# PelletMonV3.net
KiCad netlist of a schematic drawn in EasyEDA Pro
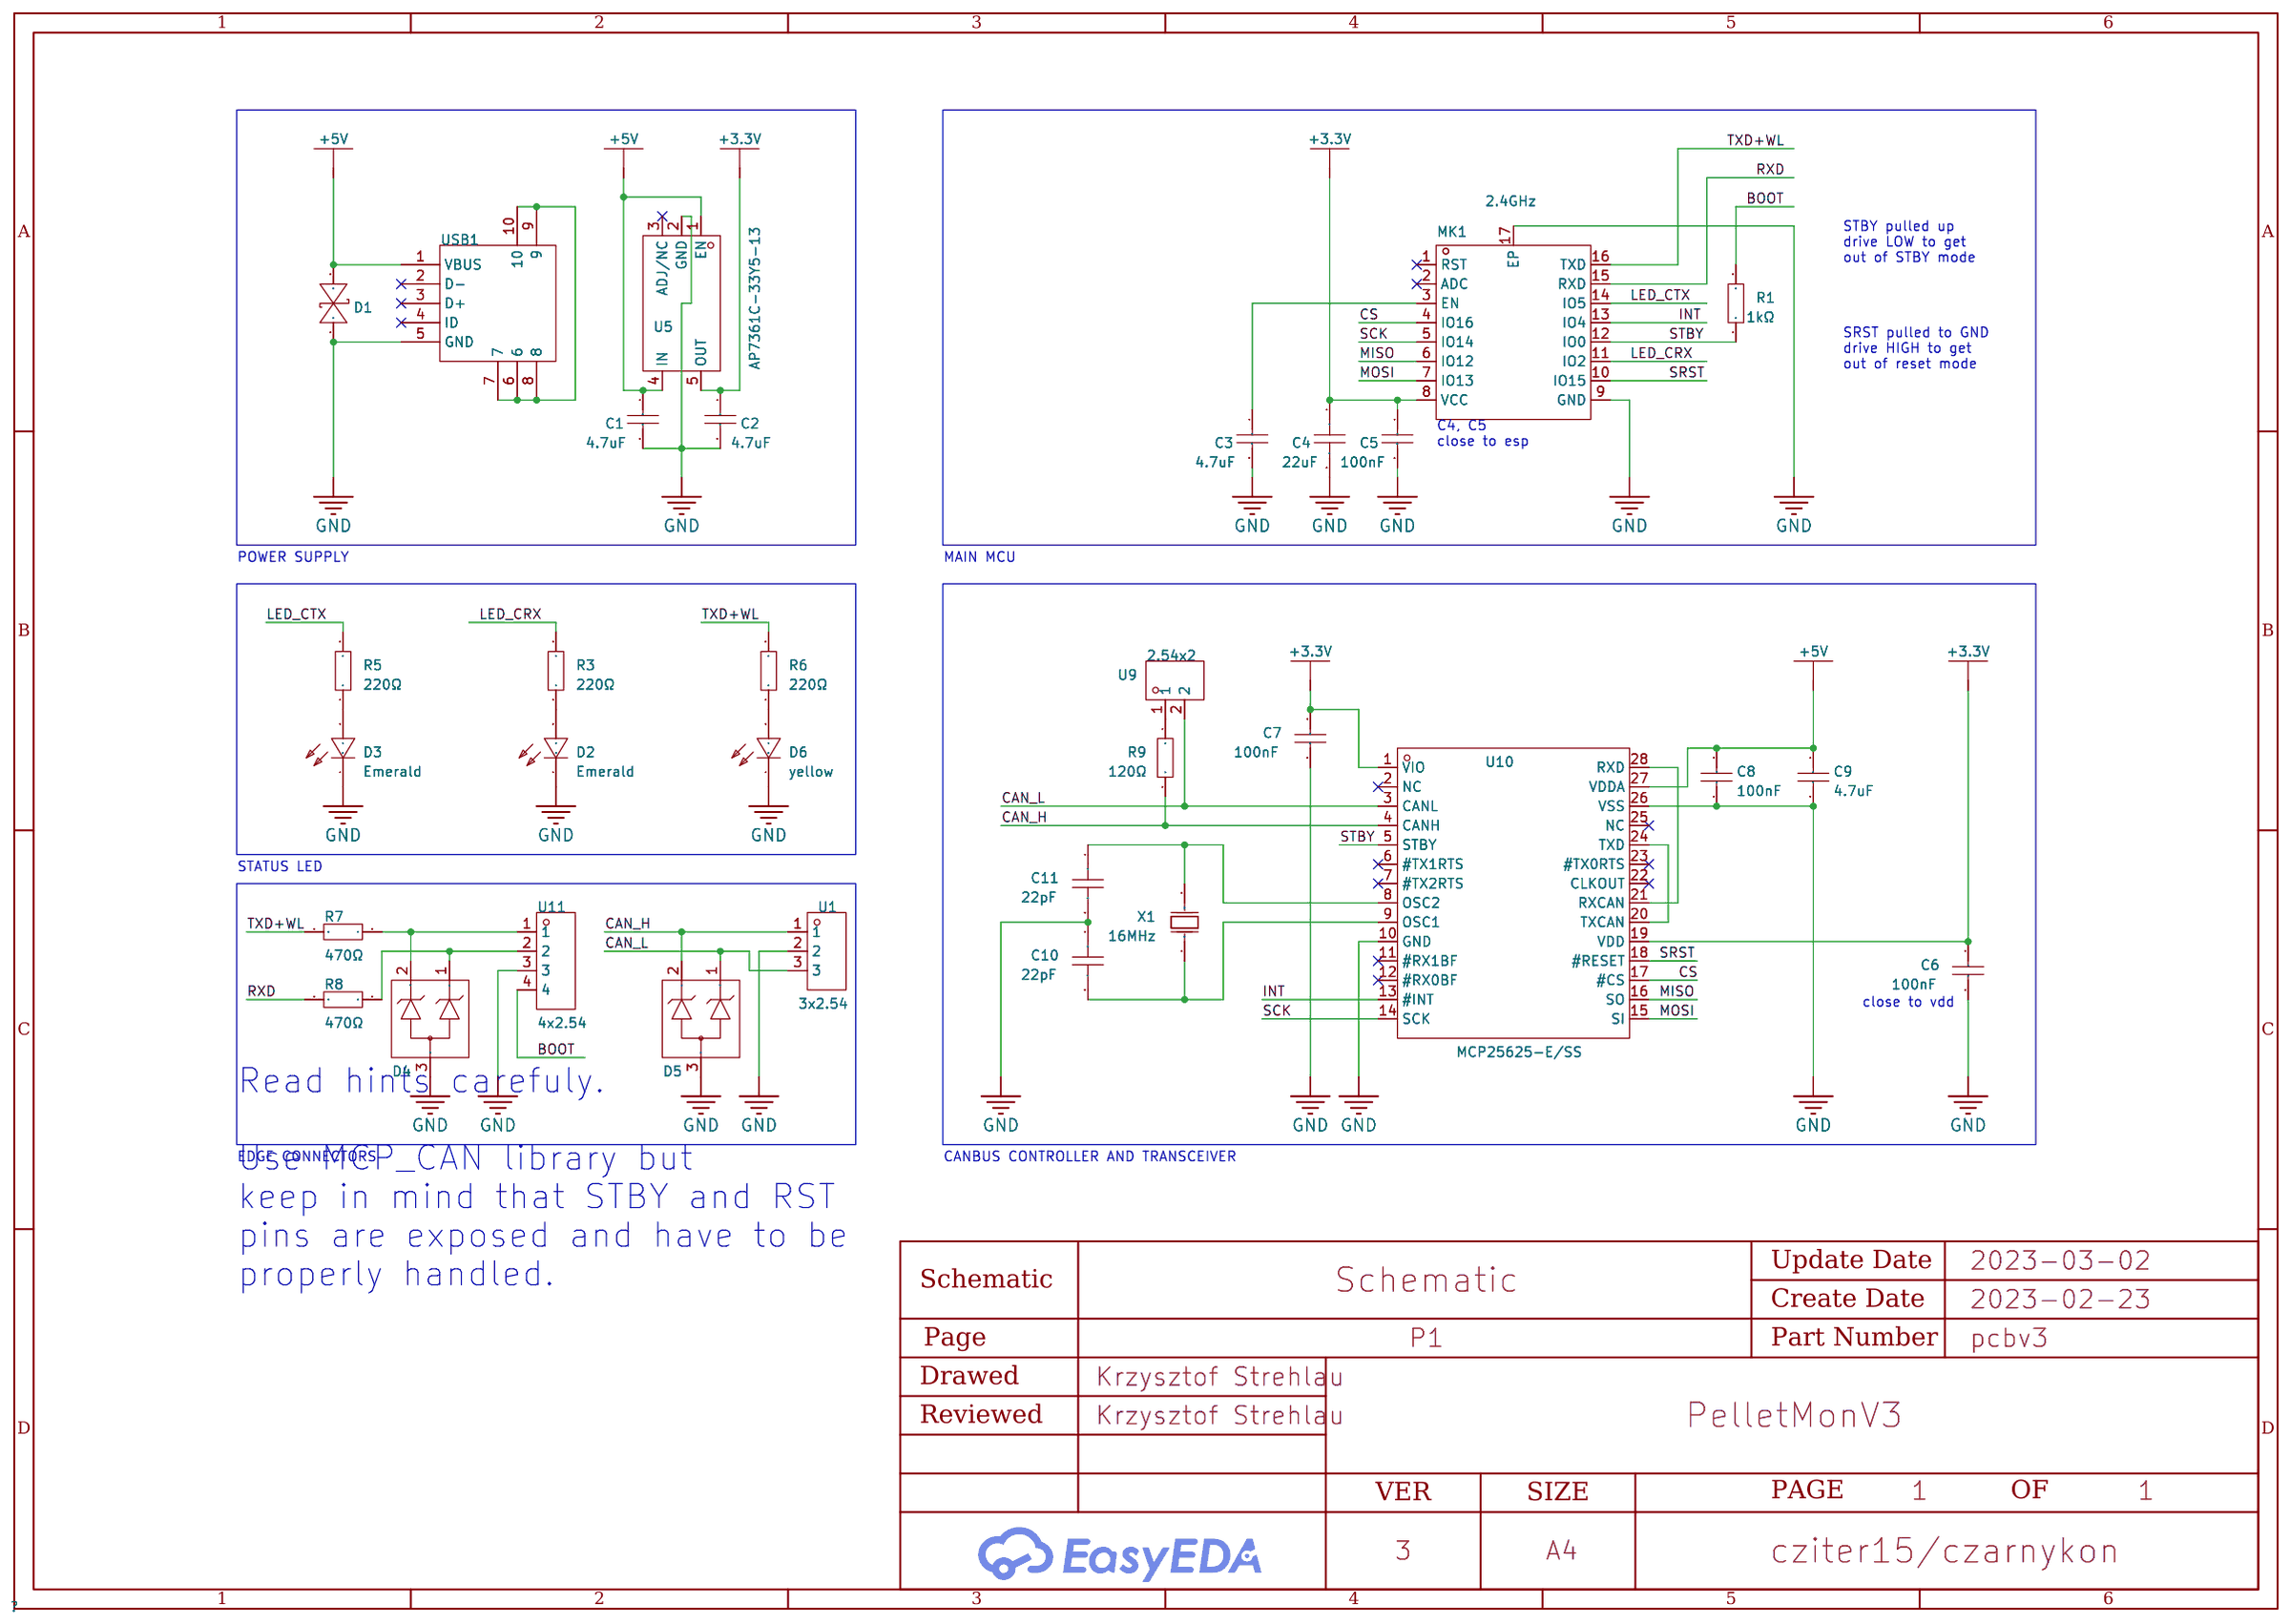
[diagram p0: schematic sheet]

(export (version "E")
  (design (tool "Eeschema 10.0.6"))
  (components
    (comp (ref "C1")
      (value "4.7uF")
      (footprint "easyedapro:C0805")
      (fields
        (field (name "Manufacturer Part") "CL21A475KAQNNNE")
        (field (name "Manufacturer") "SAMSUNG(三星)")
        (field (name "Tolerance") "±10%")
      )
      (libsource (lib "easyedapro") (part "CL21A475KAQNNNE"))
    )
    (comp (ref "C2")
      (value "4.7uF")
      (footprint "easyedapro:C0805")
      (fields
        (field (name "Manufacturer Part") "CL21A475KAQNNNE")
        (field (name "Manufacturer") "SAMSUNG(三星)")
        (field (name "Tolerance") "±10%")
      )
      (libsource (lib "easyedapro") (part "CL21A475KAQNNNE"))
    )
    (comp (ref "C3")
      (value "4.7uF")
      (footprint "easyedapro:C0805")
      (fields
        (field (name "Manufacturer Part") "CL21A475KAQNNNE")
        (field (name "Manufacturer") "SAMSUNG(三星)")
        (field (name "Tolerance") "±10%")
      )
      (libsource (lib "easyedapro") (part "CL21A475KAQNNNE"))
    )
    (comp (ref "C4")
      (value "22uF")
      (footprint "easyedapro:C0805")
      (fields
        (field (name "Manufacturer Part") "CL21A226MAQNNNE")
        (field (name "Manufacturer") "SAMSUNG(三星)")
        (field (name "Tolerance") "±20%")
      )
      (libsource (lib "easyedapro") (part "CL21A226MAQNNNE"))
    )
    (comp (ref "C5")
      (value "100nF")
      (footprint "easyedapro:C0805")
      (fields
        (field (name "Manufacturer Part") "CC0603KRX7R9BB104")
        (field (name "Manufacturer") "YAGEO(国巨)")
        (field (name "Tolerance") "±10%")
      )
      (libsource (lib "easyedapro") (part "CL21A475KAQNNNE"))
    )
    (comp (ref "C6")
      (value "100nF")
      (footprint "easyedapro:C0805")
      (fields
        (field (name "Manufacturer Part") "CC0603KRX7R9BB104")
        (field (name "Manufacturer") "YAGEO(国巨)")
        (field (name "Tolerance") "±10%")
      )
      (libsource (lib "easyedapro") (part "CL21A475KAQNNNE"))
    )
    (comp (ref "C7")
      (value "100nF")
      (footprint "easyedapro:C0805")
      (fields
        (field (name "Manufacturer Part") "CC0603KRX7R9BB104")
        (field (name "Manufacturer") "YAGEO(国巨)")
        (field (name "Tolerance") "±10%")
      )
      (libsource (lib "easyedapro") (part "CL21A475KAQNNNE"))
    )
    (comp (ref "C8")
      (value "100nF")
      (footprint "easyedapro:C0805")
      (fields
        (field (name "Manufacturer Part") "CC0603KRX7R9BB104")
        (field (name "Manufacturer") "YAGEO(国巨)")
        (field (name "Tolerance") "±10%")
      )
      (libsource (lib "easyedapro") (part "CL21A475KAQNNNE"))
    )
    (comp (ref "C9")
      (value "4.7uF")
      (footprint "easyedapro:C0805")
      (fields
        (field (name "Manufacturer Part") "CL21A475KAQNNNE")
        (field (name "Manufacturer") "SAMSUNG(三星)")
        (field (name "Tolerance") "±10%")
      )
      (libsource (lib "easyedapro") (part "CL21A475KAQNNNE"))
    )
    (comp (ref "C10")
      (value "22pF")
      (footprint "easyedapro:C0603")
      (fields
        (field (name "Manufacturer Part") "CC0603FRNPO9BN220")
        (field (name "Manufacturer") "YAGEO(国巨)")
        (field (name "Tolerance") "±1%")
      )
      (libsource (lib "easyedapro") (part "CC0603FRNPO9BN220"))
    )
    (comp (ref "C11")
      (value "22pF")
      (footprint "easyedapro:C0603")
      (fields
        (field (name "Manufacturer Part") "CC0603FRNPO9BN220")
        (field (name "Manufacturer") "YAGEO(国巨)")
      )
      (libsource (lib "easyedapro") (part "CC0603FRNPO9BN220"))
    )
    (comp (ref "D1")
      (value "PESD0603-240")
      (footprint "easyedapro:D0603-BI")
      (fields (field (name "Manufacturer") "Brightking(君耀电子)"))
      (libsource (lib "easyedapro") (part "TPESD5B5.0ST1G"))
    )
    (comp (ref "D2")
      (value "Emerald")
      (footprint "easyedapro:LED0603-RD")
      (fields
        (field (name "Manufacturer Part") "19-217/GHC-YR1S2/3T")
        (field (name "Manufacturer") "EVERLIGHT(亿光)")
      )
      (libsource (lib "easyedapro") (part "19-217/GHC-YR1S2/3T"))
    )
    (comp (ref "D3")
      (value "Emerald")
      (footprint "easyedapro:LED0603-RD")
      (fields
        (field (name "Manufacturer Part") "19-217/GHC-YR1S2/3T")
        (field (name "Manufacturer") "EVERLIGHT(亿光)")
      )
      (libsource (lib "easyedapro") (part "19-217/GHC-YR1S2/3T"))
    )
    (comp (ref "D4")
      (value "PESD3V3S2UT")
      (footprint "easyedapro:SOT-23-3_L2.9-W1.3-P1.90-LS2.4-BR")
      (fields (field (name "Manufacturer") "DOWO(东沃)"))
      (libsource (lib "easyedapro") (part "PESD3V3S2UT"))
    )
    (comp (ref "D5")
      (value "PESD2CAN")
      (footprint "easyedapro:SOT-23-3_L2.9-W1.3-P1.90-LS2.4-BR")
      (fields (field (name "Manufacturer") "DOWO(东沃)"))
      (libsource (lib "easyedapro") (part "PESD3V3S2UT"))
    )
    (comp (ref "D6")
      (value "yellow")
      (footprint "easyedapro:LED0603-RD")
      (fields
        (field (name "Manufacturer Part") "19-213/Y2C-CQ2R2L/3T(CY)")
        (field (name "Manufacturer") "EVERLIGHT(亿光)")
      )
      (libsource (lib "easyedapro") (part "19-213/Y2C-CQ2R2L/3T(CY)"))
    )
    (comp (ref "MK1")
      (value "2.4GHz")
      (footprint "easyedapro:WIRELM-SMD_ESP-07S")
      (fields (field (name "Manufacturer Part") "ESP-07S") (field (name "Manufacturer") "Ai-Thinker(安信可)"))
      (libsource (lib "easyedapro") (part "ESP-07S"))
    )
    (comp (ref "R1")
      (value "1kΩ")
      (footprint "easyedapro:R0603")
      (fields
        (field (name "Manufacturer Part") "0603WAF1001T5E")
        (field (name "Manufacturer") "UNI-ROYAL(厚声)")
        (field (name "Tolerance") "±1%")
      )
      (libsource (lib "easyedapro") (part "Res"))
    )
    (comp (ref "R3")
      (value "220Ω")
      (footprint "easyedapro:R0603")
      (fields
        (field (name "Manufacturer Part") "0603WAF2200T5E")
        (field (name "Manufacturer") "UNI-ROYAL(厚声)")
        (field (name "Tolerance") "±1%")
      )
      (libsource (lib "easyedapro") (part "0603WAF2200T5E"))
    )
    (comp (ref "R5")
      (value "220Ω")
      (footprint "easyedapro:R0603")
      (fields
        (field (name "Manufacturer Part") "0603WAF2200T5E")
        (field (name "Manufacturer") "UNI-ROYAL(厚声)")
        (field (name "Tolerance") "±1%")
      )
      (libsource (lib "easyedapro") (part "0603WAF2200T5E"))
    )
    (comp (ref "R6")
      (value "220Ω")
      (footprint "easyedapro:R0603")
      (fields
        (field (name "Manufacturer Part") "0603WAF2200T5E")
        (field (name "Manufacturer") "UNI-ROYAL(厚声)")
        (field (name "Tolerance") "±1%")
      )
      (libsource (lib "easyedapro") (part "0603WAF2200T5E"))
    )
    (comp (ref "R7")
      (value "470Ω")
      (footprint "easyedapro:R0603")
      (fields
        (field (name "Manufacturer Part") "0603WAF4700T5E")
        (field (name "Manufacturer") "UNI-ROYAL(厚声)")
        (field (name "Tolerance") "±1%")
      )
      (libsource (lib "easyedapro") (part "0805W8F1052T5E"))
    )
    (comp (ref "R8")
      (value "470Ω")
      (footprint "easyedapro:R0603")
      (fields
        (field (name "Manufacturer Part") "0603WAF4700T5E")
        (field (name "Manufacturer") "UNI-ROYAL(厚声)")
        (field (name "Tolerance") "±1%")
      )
      (libsource (lib "easyedapro") (part "0805W8F1052T5E"))
    )
    (comp (ref "R9")
      (value "120Ω")
      (footprint "easyedapro:R0603")
      (fields
        (field (name "Manufacturer Part") "0603WAF1200T5E")
        (field (name "Manufacturer") "UNI-ROYAL(厚声)")
        (field (name "Tolerance") "±1%")
      )
      (libsource (lib "easyedapro") (part "Res"))
    )
    (comp (ref "U1")
      (value "3x2.54")
      (footprint "easyedapro:CONN-TH_DB125-2.54-3P-GN")
      (fields (field (name "Manufacturer") "DIBO(地博电气)"))
      (libsource (lib "easyedapro") (part "DB125-2.54-3P-GN"))
    )
    (comp (ref "U5")
      (value "AP7361C-33Y5-13")
      (footprint "easyedapro:SOT-89-5_L4.5-W2.5-P1.50-LS4.5-BR")
      (fields (field (name "Manufacturer") "DIODES(美台)"))
      (libsource (lib "easyedapro") (part "AP7361C-33Y5-13"))
    )
    (comp (ref "U9")
      (value "2.54x2")
      (footprint "easyedapro:HDR-TH_2P-P2.54-V-M")
      (fields (field (name "Manufacturer") "DIBO(地博电气)"))
      (libsource (lib "easyedapro") (part "2.54-1*2"))
    )
    (comp (ref "U10")
      (value "MCP25625-E/SS")
      (footprint "easyedapro:SSOP-28_L10.2-W5.3-P0.65-LS7.8-BL")
      (description "Type:Transceiver Supply Voltage:2.7V~5.5V Supply Voltage:2.7V~5.5V")
      (fields (field (name "Manufacturer") "MICROCHIP(美国微芯)"))
      (libsource (lib "easyedapro") (part "MCP25625-E/SS"))
    )
    (comp (ref "U11")
      (value "4x2.54")
      (footprint "easyedapro:CONN-TH_DB125-2.54-4P-GN")
      (fields (field (name "Manufacturer") "DIBO(地博电气)"))
      (libsource (lib "easyedapro") (part "DB125-2.54-4P-GN"))
    )
    (comp (ref "USB1")
      (value "475900001")
      (footprint "easyedapro:MICRO-USB-SMD_47590-0001")
      (description "Connector Type:Micro-AB Standard:- Gender:Female Number of Contacts:5 Number of Ports:1")
      (fields (field (name "Manufacturer") "MOLEX"))
      (libsource (lib "easyedapro") (part "47590-0001"))
    )
    (comp (ref "X1")
      (value "16MHz")
      (footprint "easyedapro:OSC-SMD_L5.0-W3.2")
      (fields (field (name "Manufacturer Part") "X503216MSB2GI") (field (name "Manufacturer") "YXC(扬兴晶振)"))
      (libsource (lib "easyedapro") (part "X503216MSB2GI"))
    )
  )
  (nets
    (net (code "1") (name "+3.3V") (class "Default")
      (node (ref "C2") (pin "1") (pinfunction "1_1") (pintype "input"))
      (node (ref "C4") (pin "1") (pinfunction "1_1") (pintype "input"))
      (node (ref "C5") (pin "1") (pinfunction "1_1") (pintype "input"))
      (node (ref "C6") (pin "2") (pinfunction "2_2") (pintype "input"))
      (node (ref "C7") (pin "2") (pinfunction "2_2") (pintype "input"))
      (node (ref "MK1") (pin "8") (pinfunction "VCC_8") (pintype "input"))
      (node (ref "U10") (pin "1") (pinfunction "VIO_1") (pintype "input"))
      (node (ref "U10") (pin "19") (pinfunction "VDD_19") (pintype "input"))
      (node (ref "U5") (pin "5") (pinfunction "OUT_5") (pintype "input"))
    )
    (net (code "2") (name "+5V") (class "Default")
      (node (ref "C1") (pin "1") (pinfunction "1_1") (pintype "input"))
      (node (ref "C8") (pin "2") (pinfunction "2_2") (pintype "input"))
      (node (ref "C9") (pin "1") (pinfunction "1_1") (pintype "input"))
      (node (ref "D1") (pin "2") (pinfunction "2_2") (pintype "input"))
      (node (ref "U10") (pin "27") (pinfunction "VDDA_27") (pintype "input"))
      (node (ref "U5") (pin "1") (pinfunction "EN_1") (pintype "input"))
      (node (ref "U5") (pin "4") (pinfunction "IN_4") (pintype "input"))
      (node (ref "USB1") (pin "1") (pinfunction "VBUS_1") (pintype "input"))
    )
    (net (code "3") (name "/BOOT") (class "Default")
      (node (ref "R1") (pin "2") (pinfunction "2_2") (pintype "input"))
      (node (ref "U11") (pin "4") (pinfunction "4_4") (pintype "input"))
    )
    (net (code "4") (name "/CAN_H") (class "Default")
      (node (ref "D5") (pin "2") (pinfunction "K2_2") (pintype "input"))
      (node (ref "R9") (pin "2") (pinfunction "2_2") (pintype "input"))
      (node (ref "U1") (pin "1") (pinfunction "1_1") (pintype "input"))
      (node (ref "U10") (pin "4") (pinfunction "CANH_4") (pintype "input"))
    )
    (net (code "5") (name "/CAN_L") (class "Default")
      (node (ref "D5") (pin "1") (pinfunction "K1_1") (pintype "input"))
      (node (ref "U1") (pin "3") (pinfunction "3_3") (pintype "input"))
      (node (ref "U10") (pin "3") (pinfunction "CANL_3") (pintype "input"))
      (node (ref "U9") (pin "2") (pinfunction "2_2") (pintype "input"))
    )
    (net (code "6") (name "/CS") (class "Default")
      (node (ref "MK1") (pin "4") (pinfunction "IO16_4") (pintype "input"))
      (node (ref "U10") (pin "17") (pinfunction "#CS_17") (pintype "input"))
    )
    (net (code "7") (name "/INT") (class "Default")
      (node (ref "MK1") (pin "13") (pinfunction "IO4_13") (pintype "input"))
      (node (ref "U10") (pin "13") (pinfunction "#INT_13") (pintype "input"))
    )
    (net (code "8") (name "/LED_CRX") (class "Default")
      (node (ref "MK1") (pin "11") (pinfunction "IO2_11") (pintype "input"))
      (node (ref "R3") (pin "2") (pinfunction "2_2") (pintype "input"))
    )
    (net (code "9") (name "/LED_CTX") (class "Default")
      (node (ref "MK1") (pin "14") (pinfunction "IO5_14") (pintype "input"))
      (node (ref "R5") (pin "2") (pinfunction "2_2") (pintype "input"))
    )
    (net (code "10") (name "/MISO") (class "Default")
      (node (ref "MK1") (pin "6") (pinfunction "IO12_6") (pintype "input"))
      (node (ref "U10") (pin "16") (pinfunction "SO_16") (pintype "input"))
    )
    (net (code "11") (name "/MOSI") (class "Default")
      (node (ref "MK1") (pin "7") (pinfunction "IO13_7") (pintype "input"))
      (node (ref "U10") (pin "15") (pinfunction "SI_15") (pintype "input"))
    )
    (net (code "12") (name "/RXD") (class "Default")
      (node (ref "MK1") (pin "15") (pinfunction "RXD_15") (pintype "input"))
      (node (ref "R8") (pin "2") (pinfunction "2_2") (pintype "input"))
    )
    (net (code "13") (name "/SCK") (class "Default")
      (node (ref "MK1") (pin "5") (pinfunction "IO14_5") (pintype "input"))
      (node (ref "U10") (pin "14") (pinfunction "SCK_14") (pintype "input"))
    )
    (net (code "14") (name "/SRST") (class "Default")
      (node (ref "MK1") (pin "10") (pinfunction "IO15_10") (pintype "input"))
      (node (ref "U10") (pin "18") (pinfunction "#RESET_18") (pintype "input"))
    )
    (net (code "15") (name "/STBY") (class "Default")
      (node (ref "MK1") (pin "12") (pinfunction "IO0_12") (pintype "input"))
      (node (ref "R1") (pin "1") (pinfunction "1_1") (pintype "input"))
      (node (ref "U10") (pin "5") (pinfunction "STBY_5") (pintype "input"))
    )
    (net (code "16") (name "/TXD+WL") (class "Default")
      (node (ref "MK1") (pin "16") (pinfunction "TXD_16") (pintype "input"))
      (node (ref "R6") (pin "2") (pinfunction "2_2") (pintype "input"))
      (node (ref "R7") (pin "2") (pinfunction "2_2") (pintype "input"))
    )
    (net (code "17") (name "GND") (class "Default")
      (node (ref "C1") (pin "2") (pinfunction "2_2") (pintype "input"))
      (node (ref "C10") (pin "1") (pinfunction "1_1") (pintype "input"))
      (node (ref "C11") (pin "2") (pinfunction "2_2") (pintype "input"))
      (node (ref "C2") (pin "2") (pinfunction "2_2") (pintype "input"))
      (node (ref "C3") (pin "2") (pinfunction "2_2") (pintype "input"))
      (node (ref "C4") (pin "2") (pinfunction "2_2") (pintype "input"))
      (node (ref "C5") (pin "2") (pinfunction "2_2") (pintype "input"))
      (node (ref "C6") (pin "1") (pinfunction "1_1") (pintype "input"))
      (node (ref "C7") (pin "1") (pinfunction "1_1") (pintype "input"))
      (node (ref "C8") (pin "1") (pinfunction "1_1") (pintype "input"))
      (node (ref "C9") (pin "2") (pinfunction "2_2") (pintype "input"))
      (node (ref "D1") (pin "1") (pinfunction "1_1") (pintype "input"))
      (node (ref "D2") (pin "1") (pinfunction "C_1") (pintype "input"))
      (node (ref "D3") (pin "1") (pinfunction "C_1") (pintype "input"))
      (node (ref "D4") (pin "3") (pinfunction "CA_3") (pintype "input"))
      (node (ref "D5") (pin "3") (pinfunction "CA_3") (pintype "input"))
      (node (ref "D6") (pin "1") (pinfunction "C_1") (pintype "input"))
      (node (ref "MK1") (pin "17") (pinfunction "EP_17") (pintype "input"))
      (node (ref "MK1") (pin "9") (pinfunction "GND_9") (pintype "input"))
      (node (ref "U1") (pin "2") (pinfunction "2_2") (pintype "input"))
      (node (ref "U10") (pin "10") (pinfunction "GND_10") (pintype "input"))
      (node (ref "U10") (pin "26") (pinfunction "VSS_26") (pintype "input"))
      (node (ref "U11") (pin "3") (pinfunction "3_3") (pintype "input"))
      (node (ref "U5") (pin "2") (pinfunction "GND_2") (pintype "input"))
      (node (ref "USB1") (pin "5") (pinfunction "GND_5") (pintype "input"))
    )
    (net (code "18") (name "Net-(D2-A)") (class "Default")
      (node (ref "D2") (pin "2") (pinfunction "A_2") (pintype "input"))
      (node (ref "R3") (pin "1") (pinfunction "1_1") (pintype "input"))
    )
    (net (code "19") (name "Net-(D3-A)") (class "Default")
      (node (ref "D3") (pin "2") (pinfunction "A_2") (pintype "input"))
      (node (ref "R5") (pin "1") (pinfunction "1_1") (pintype "input"))
    )
    (net (code "20") (name "Net-(D4-K1)") (class "Default")
      (node (ref "D4") (pin "1") (pinfunction "K1_1") (pintype "input"))
      (node (ref "R8") (pin "1") (pinfunction "1_1") (pintype "input"))
      (node (ref "U11") (pin "2") (pinfunction "2_2") (pintype "input"))
    )
    (net (code "21") (name "Net-(D4-K2)") (class "Default")
      (node (ref "D4") (pin "2") (pinfunction "K2_2") (pintype "input"))
      (node (ref "R7") (pin "1") (pinfunction "1_1") (pintype "input"))
      (node (ref "U11") (pin "1") (pinfunction "1_1") (pintype "input"))
    )
    (net (code "22") (name "Net-(D6-A)") (class "Default")
      (node (ref "D6") (pin "2") (pinfunction "A_2") (pintype "input"))
      (node (ref "R6") (pin "1") (pinfunction "1_1") (pintype "input"))
    )
    (net (code "23") (name "Net-(MK1-EN)") (class "Default")
      (node (ref "C3") (pin "1") (pinfunction "1_1") (pintype "input"))
      (node (ref "MK1") (pin "3") (pinfunction "EN_3") (pintype "input"))
    )
    (net (code "24") (name "Net-(R9-Pad1)") (class "Default")
      (node (ref "R9") (pin "1") (pinfunction "1_1") (pintype "input"))
      (node (ref "U9") (pin "1") (pinfunction "1_1") (pintype "input"))
    )
    (net (code "25") (name "Net-(U10-OSC1)") (class "Default")
      (node (ref "C10") (pin "2") (pinfunction "2_2") (pintype "input"))
      (node (ref "U10") (pin "9") (pinfunction "OSC1_9") (pintype "input"))
      (node (ref "X1") (pin "1") (pinfunction "OSC1_1") (pintype "input"))
    )
    (net (code "26") (name "Net-(U10-OSC2)") (class "Default")
      (node (ref "C11") (pin "1") (pinfunction "1_1") (pintype "input"))
      (node (ref "U10") (pin "8") (pinfunction "OSC2_8") (pintype "input"))
      (node (ref "X1") (pin "2") (pinfunction "OSC2_2") (pintype "input"))
    )
    (net (code "27") (name "Net-(U10-RXCAN)") (class "Default")
      (node (ref "U10") (pin "21") (pinfunction "RXCAN_21") (pintype "input"))
      (node (ref "U10") (pin "28") (pinfunction "RXD_28") (pintype "input"))
    )
    (net (code "28") (name "Net-(U10-TXCAN)") (class "Default")
      (node (ref "U10") (pin "20") (pinfunction "TXCAN_20") (pintype "input"))
      (node (ref "U10") (pin "24") (pinfunction "TXD_24") (pintype "input"))
    )
    (net (code "29") (name "Net-(USB1-Pad10)") (class "Default")
      (node (ref "USB1") (pin "10") (pinfunction "10_10") (pintype "input"))
      (node (ref "USB1") (pin "6") (pinfunction "6_6") (pintype "input"))
      (node (ref "USB1") (pin "7") (pinfunction "7_7") (pintype "input"))
      (node (ref "USB1") (pin "8") (pinfunction "8_8") (pintype "input"))
      (node (ref "USB1") (pin "9") (pinfunction "9_9") (pintype "input"))
    )
    (net (code "30") (name "unconnected-(MK1-ADC-Pad2)") (class "Default")
      (node (ref "MK1") (pin "2") (pinfunction "ADC_2") (pintype "input+no_connect"))
    )
    (net (code "31") (name "unconnected-(MK1-RST-Pad1)") (class "Default")
      (node (ref "MK1") (pin "1") (pinfunction "RST_1") (pintype "input+no_connect"))
    )
    (net (code "32") (name "unconnected-(U5-ADJ{slash}NC-Pad3)") (class "Default")
      (node (ref "U5") (pin "3") (pinfunction "ADJ/NC_3") (pintype "input+no_connect"))
    )
    (net (code "33") (name "unconnected-(U10-#RX0BF-Pad12)") (class "Default")
      (node (ref "U10") (pin "12") (pinfunction "#RX0BF_12") (pintype "input+no_connect"))
    )
    (net (code "34") (name "unconnected-(U10-#RX1BF-Pad11)") (class "Default")
      (node (ref "U10") (pin "11") (pinfunction "#RX1BF_11") (pintype "input+no_connect"))
    )
    (net (code "35") (name "unconnected-(U10-#TX0RTS-Pad23)") (class "Default")
      (node (ref "U10") (pin "23") (pinfunction "#TX0RTS_23") (pintype "input+no_connect"))
    )
    (net (code "36") (name "unconnected-(U10-#TX1RTS-Pad6)") (class "Default")
      (node (ref "U10") (pin "6") (pinfunction "#TX1RTS_6") (pintype "input+no_connect"))
    )
    (net (code "37") (name "unconnected-(U10-#TX2RTS-Pad7)") (class "Default")
      (node (ref "U10") (pin "7") (pinfunction "#TX2RTS_7") (pintype "input+no_connect"))
    )
    (net (code "38") (name "unconnected-(U10-CLKOUT-Pad22)") (class "Default")
      (node (ref "U10") (pin "22") (pinfunction "CLKOUT_22") (pintype "input+no_connect"))
    )
    (net (code "39") (name "unconnected-(U10-NC-Pad2)") (class "Default")
      (node (ref "U10") (pin "2") (pinfunction "NC_2") (pintype "input+no_connect"))
    )
    (net (code "40") (name "unconnected-(U10-NC-Pad25)") (class "Default")
      (node (ref "U10") (pin "25") (pinfunction "NC_25") (pintype "input+no_connect"))
    )
    (net (code "41") (name "unconnected-(USB1-D+-Pad3)") (class "Default")
      (node (ref "USB1") (pin "3") (pinfunction "D+_3") (pintype "input+no_connect"))
    )
    (net (code "42") (name "unconnected-(USB1-D--Pad2)") (class "Default")
      (node (ref "USB1") (pin "2") (pinfunction "D-_2") (pintype "input+no_connect"))
    )
    (net (code "43") (name "unconnected-(USB1-ID-Pad4)") (class "Default")
      (node (ref "USB1") (pin "4") (pinfunction "ID_4") (pintype "input+no_connect"))
    )
  )
)
